# 2023_04_07_SCH_Sensor.net
KiCad netlist of a schematic drawn in EasyEDA
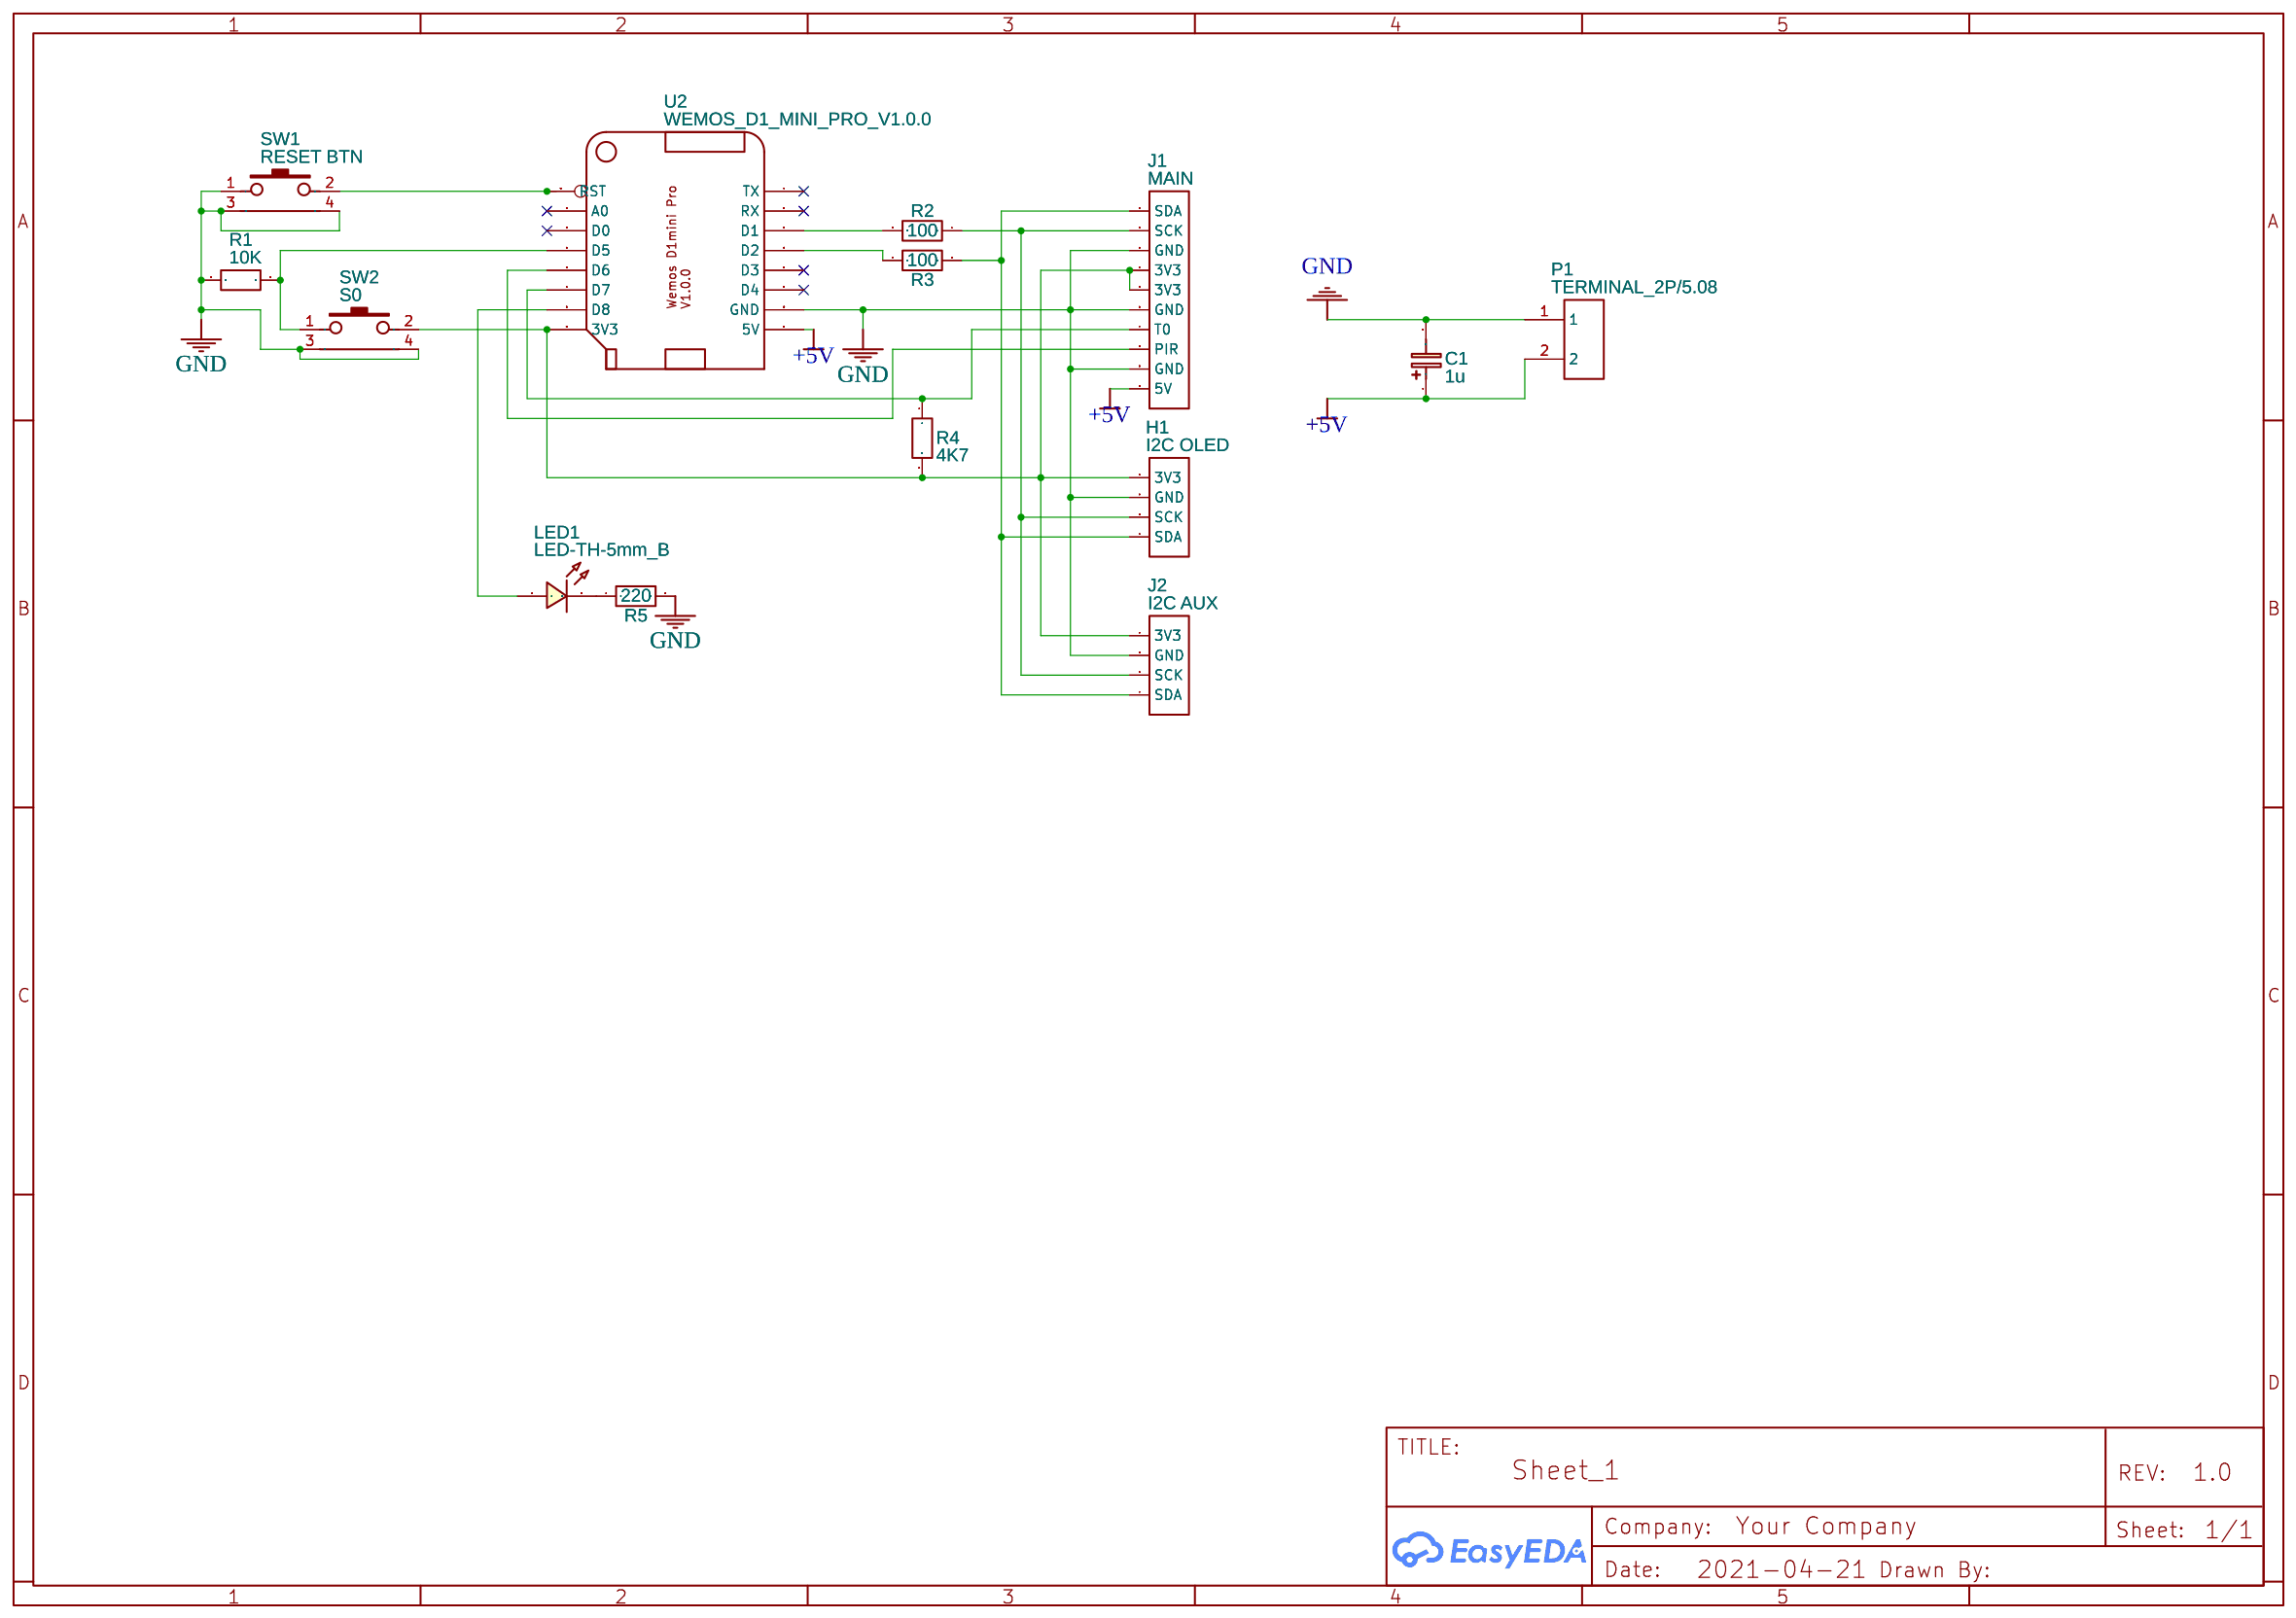
[diagram p0: Main]
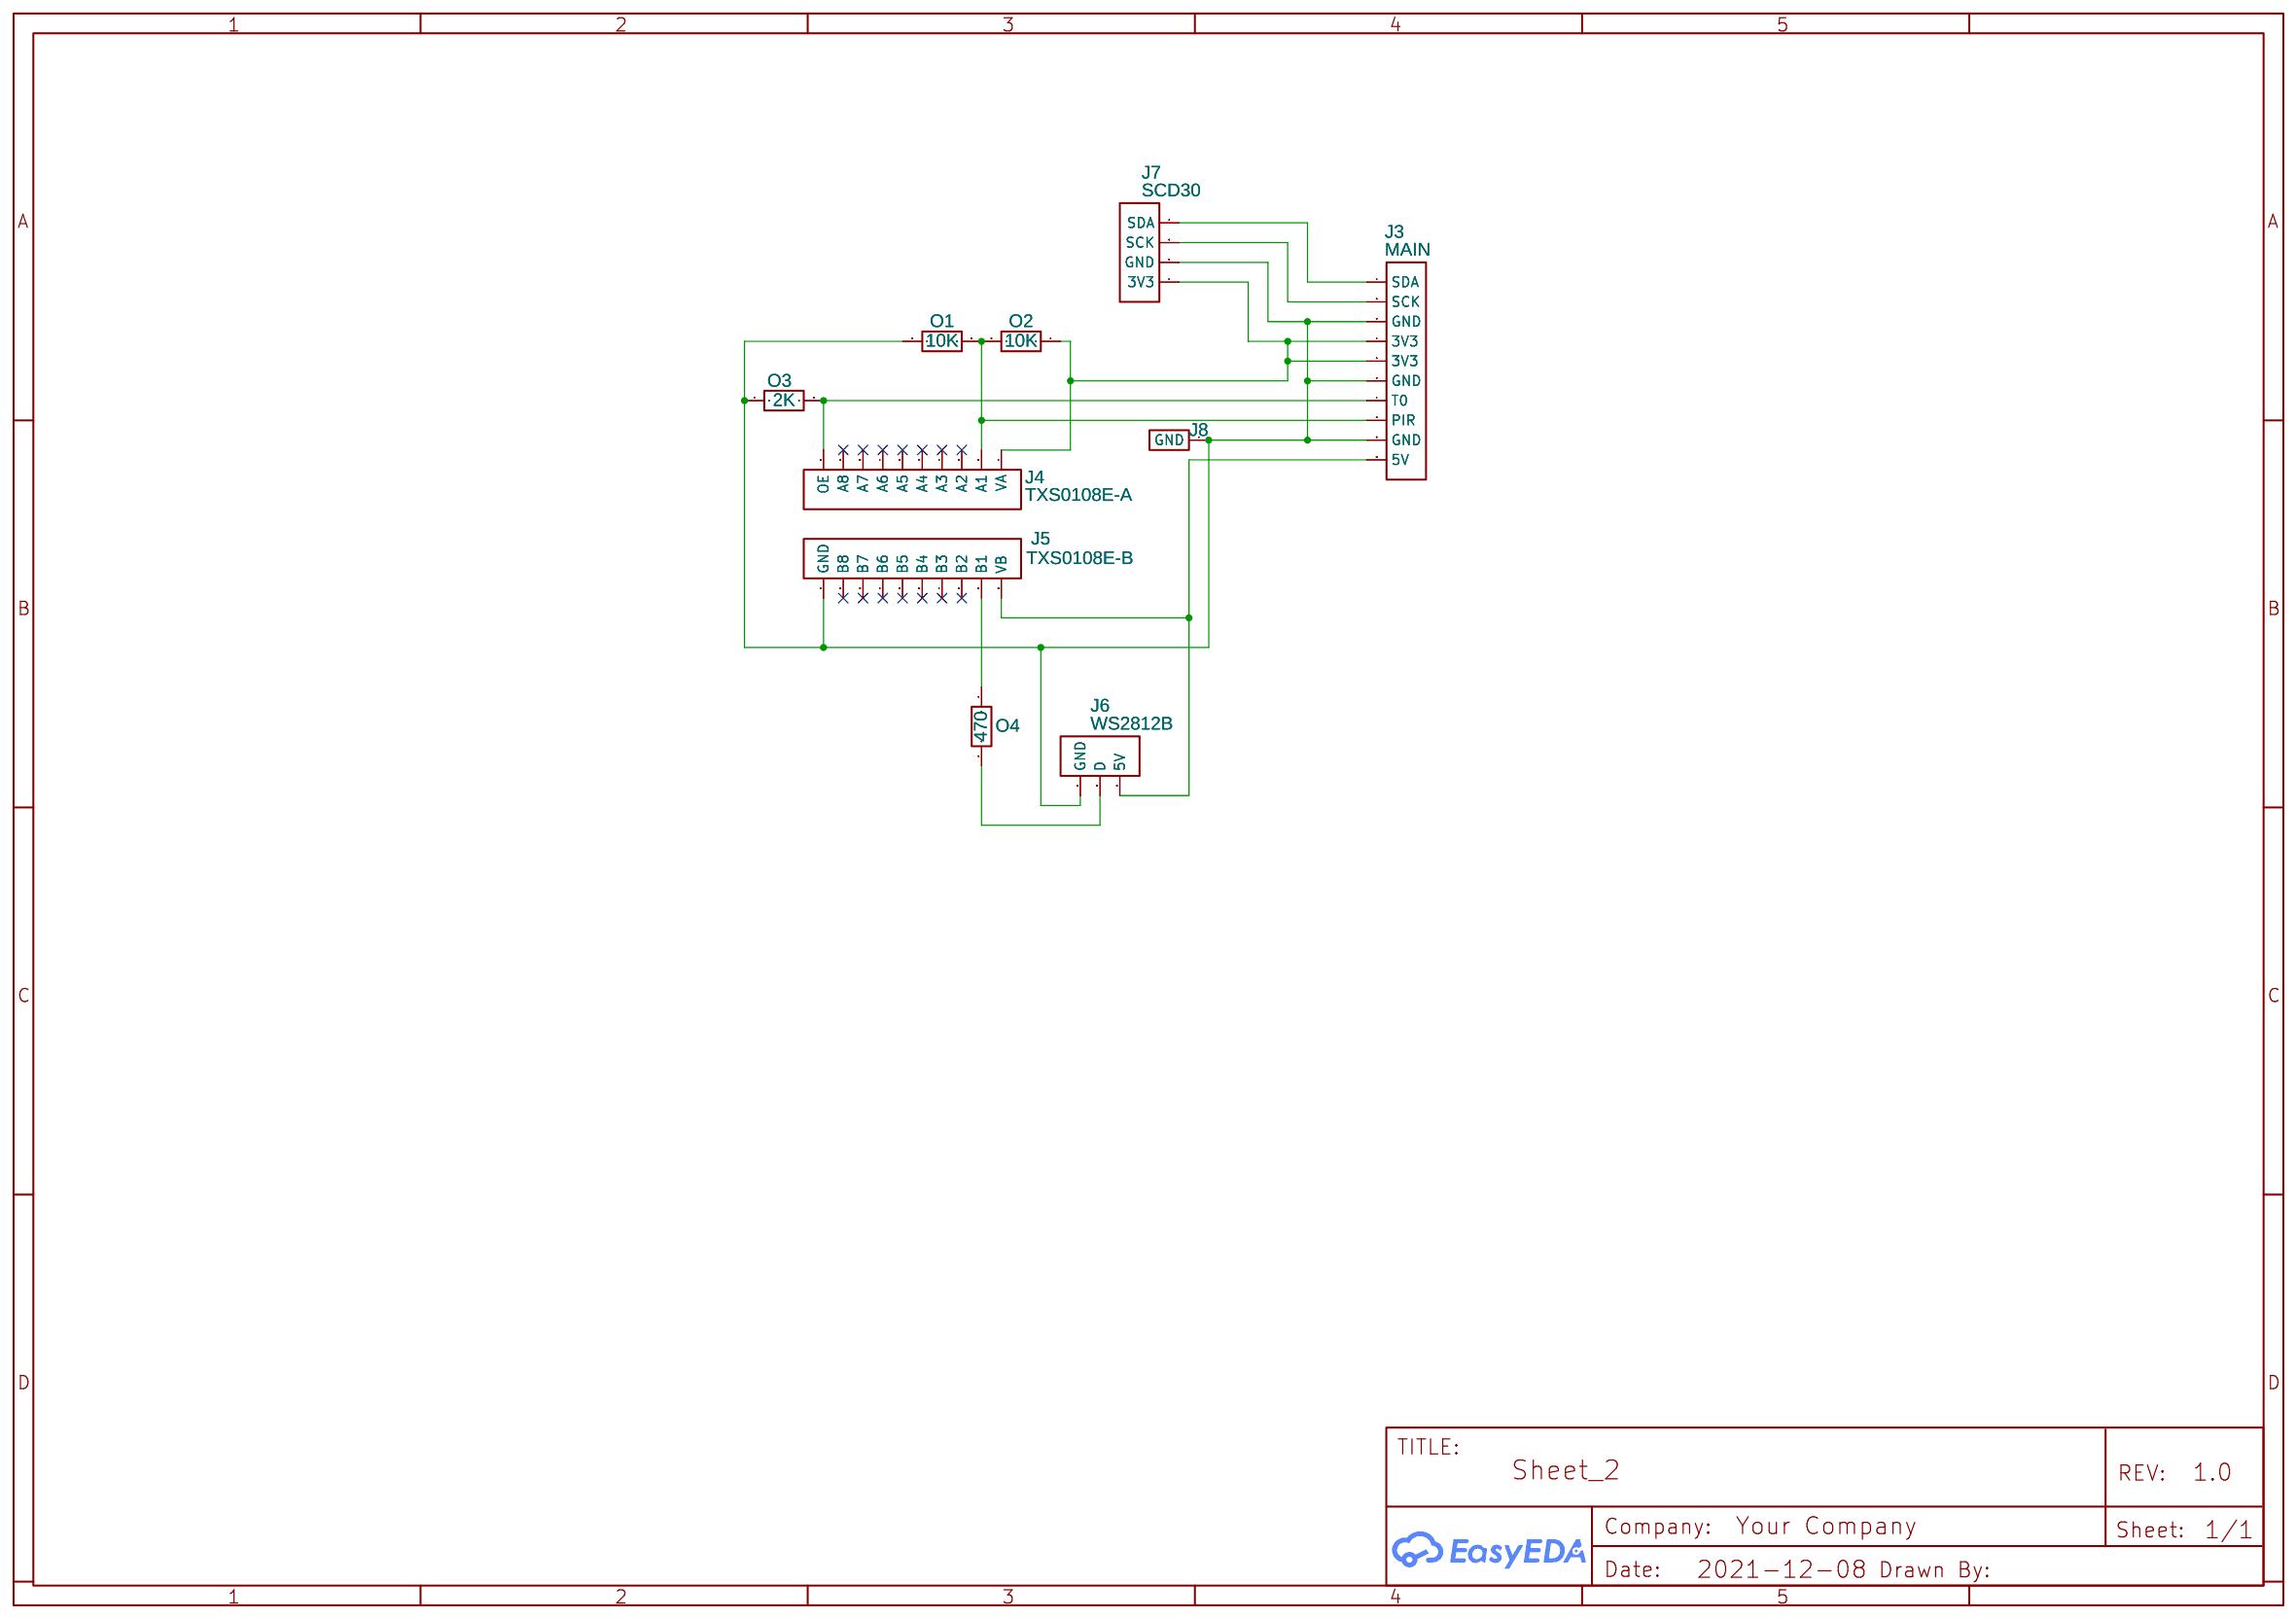
[diagram p1: Aux_C02]

(export (version "E")
  (design (tool "Eeschema 10.0.6"))
  (components
    (comp (ref "C1") (value "1u") (libsource (lib "") (part "CE_TH_D10.0×F5.0_EU")))
    (comp (ref "H1")
      (value "I2C OLED")
      (fields (field (name "BOM_Supplier Part") "C225501"))
      (libsource (lib "") (part "HDR-F-2.54_1x4"))
    )
    (comp (ref "J1")
      (value "MAIN")
      (fields (field (name "BOM_Supplier Part") "C57369"))
      (libsource (lib "") (part "HDR-M-2.54_1x10"))
    )
    (comp (ref "J2")
      (value "I2C AUX")
      (fields (field (name "BOM_Supplier Part") "C124378"))
      (libsource (lib "") (part "HDR-M-2.54_1x4"))
    )
    (comp (ref "LED1") (value "LED-TH-5mm_B") (libsource (lib "") (part "LED-TH-5mm_B")))
    (comp (ref "P1")
      (value "TERMINAL_2P/5.08")
      (fields (field (name "BOM_Manufacturer Part") "Screw terminal 2p"))
      (libsource (lib "") (part "TERMINAL_2P/5.08"))
    )
    (comp (ref "R1") (value "10K") (libsource (lib "") (part "R_AXIAL-0.3_EU_1")))
    (comp (ref "R2") (value "100") (libsource (lib "") (part "R_AXIAL-0.3_EU_1")))
    (comp (ref "R3") (value "100") (libsource (lib "") (part "R_AXIAL-0.3_EU")))
    (comp (ref "R4") (value "4K7") (libsource (lib "") (part "R_AXIAL-0.3_EU_2")))
    (comp (ref "R5") (value "220") (libsource (lib "") (part "R_AXIAL-0.3_EU")))
    (comp (ref "SW1")
      (value "RESET BTN")
      (fields
        (field (name "BOM_Manufacturer Part") "Switch,6*6*9Plastic head,260G, 0.25mm,Side bracket")
        (field (name "BOM_Supplier Part") "C71842")
      )
      (libsource (lib "") (part "Button-6x6x9-Right-Angle"))
    )
    (comp (ref "SW2")
      (value "S0")
      (fields
        (field (name "BOM_Manufacturer Part") "Switch,6*6*9Plastic head,260G, 0.25mm,Side bracket")
        (field (name "BOM_Supplier Part") "C71842")
      )
      (libsource (lib "") (part "Button-6x6x9-Right-Angle"))
    )
    (comp (ref "U2")
      (value "WEMOS_D1_MINI_PRO_V1.0.0")
      (fields
        (field (name "BOM_Manufacturer Part") "WeMos D1 Mini Pro")
        (field (name "BOM_Supplier Part") "undefined")
      )
      (libsource (lib "") (part "WEMOS_D1_MINI_PRO_V1.0.0"))
    )
    (comp (ref "J3")
      (value "MAIN")
      (fields (field (name "BOM_Supplier Part") "C57369"))
      (libsource (lib "") (part "HDR-M-2.54_1x10"))
    )
    (comp (ref "J4")
      (value "TXS0108E-A")
      (fields (field (name "BOM_Supplier Part") "C57369"))
      (libsource (lib "") (part "HDR-M-2.54_1x10_1"))
    )
    (comp (ref "J5")
      (value "TXS0108E-B")
      (fields (field (name "BOM_Supplier Part") "C57369"))
      (libsource (lib "") (part "HDR-M-2.54_1x10_2"))
    )
    (comp (ref "J6")
      (value "WS2812B")
      (fields (field (name "BOM_Supplier Part") "C180248"))
      (libsource (lib "") (part "HDR-M-2.54_1x3"))
    )
    (comp (ref "J7")
      (value "SCD30")
      (fields (field (name "BOM_Supplier Part") "C124378"))
      (libsource (lib "") (part "HDR-M-2.54_1x4"))
    )
    (comp (ref "J8")
      (value "HDR-M-2.54_1x1")
      (fields (field (name "BOM_Supplier Part") "C81276"))
      (libsource (lib "") (part "HDR-M-2.54_1x1"))
    )
    (comp (ref "O1") (value "10K") (libsource (lib "") (part "R_AXIAL-0.3_EU_1")))
    (comp (ref "O2") (value "10K") (libsource (lib "") (part "R_AXIAL-0.3_EU")))
    (comp (ref "O3") (value "2K") (libsource (lib "") (part "R_AXIAL-0.3_EU_1")))
    (comp (ref "O4") (value "470") (libsource (lib "") (part "R_AXIAL-0.3_EU_2")))
  )
  (nets
    (net (code "1") (name "+5V") (class "Default")
      (node (ref "C1") (pin "1") (pinfunction "1_1") (pintype "unspecified"))
      (node (ref "J1") (pin "10") (pinfunction "5V_10") (pintype "unspecified"))
      (node (ref "P1") (pin "2") (pinfunction "2_2") (pintype "unspecified"))
      (node (ref "U2") (pin "5V") (pinfunction "5V_5V") (pintype "unspecified"))
    )
    (net (code "2") (name "GND") (class "Default")
      (node (ref "C1") (pin "2") (pinfunction "2_2") (pintype "unspecified"))
      (node (ref "H1") (pin "2") (pinfunction "GND_2") (pintype "unspecified"))
      (node (ref "J1") (pin "3") (pinfunction "GND_3") (pintype "unspecified"))
      (node (ref "J1") (pin "6") (pinfunction "GND_6") (pintype "unspecified"))
      (node (ref "J1") (pin "9") (pinfunction "GND_9") (pintype "unspecified"))
      (node (ref "J2") (pin "2") (pinfunction "GND_2") (pintype "unspecified"))
      (node (ref "P1") (pin "1") (pinfunction "1_1") (pintype "unspecified"))
      (node (ref "R1") (pin "2") (pinfunction "2_2") (pintype "unspecified"))
      (node (ref "R5") (pin "2") (pinfunction "2_2") (pintype "unspecified"))
      (node (ref "SW1") (pin "1") (pinfunction "1_1") (pintype "input"))
      (node (ref "SW1") (pin "3") (pinfunction "3_3") (pintype "input"))
      (node (ref "SW1") (pin "4") (pinfunction "4_4") (pintype "input"))
      (node (ref "SW2") (pin "3") (pinfunction "3_3") (pintype "input"))
      (node (ref "SW2") (pin "4") (pinfunction "4_4") (pintype "input"))
      (node (ref "U2") (pin "GND") (pinfunction "GND_GND") (pintype "unspecified"))
    )
    (net (code "3") (name "Net-(H1-3V3)") (class "Default")
      (node (ref "H1") (pin "1") (pinfunction "3V3_1") (pintype "unspecified"))
      (node (ref "J1") (pin "4") (pinfunction "3V3_4") (pintype "unspecified"))
      (node (ref "J1") (pin "5") (pinfunction "3V3_5") (pintype "unspecified"))
      (node (ref "J2") (pin "1") (pinfunction "3V3_1") (pintype "unspecified"))
      (node (ref "R4") (pin "2") (pinfunction "2_2") (pintype "unspecified"))
      (node (ref "SW2") (pin "2") (pinfunction "2_2") (pintype "input"))
      (node (ref "U2") (pin "3V3") (pinfunction "3V3_3V3") (pintype "unspecified"))
    )
    (net (code "4") (name "Net-(H1-SCK)") (class "Default")
      (node (ref "H1") (pin "3") (pinfunction "SCK_3") (pintype "unspecified"))
      (node (ref "J1") (pin "2") (pinfunction "SCK_2") (pintype "unspecified"))
      (node (ref "J2") (pin "3") (pinfunction "SCK_3") (pintype "unspecified"))
      (node (ref "R2") (pin "1") (pinfunction "1_1") (pintype "unspecified"))
    )
    (net (code "5") (name "Net-(H1-SDA)") (class "Default")
      (node (ref "H1") (pin "4") (pinfunction "SDA_4") (pintype "unspecified"))
      (node (ref "J1") (pin "1") (pinfunction "SDA_1") (pintype "unspecified"))
      (node (ref "J2") (pin "4") (pinfunction "SDA_4") (pintype "unspecified"))
      (node (ref "R3") (pin "2") (pinfunction "2_2") (pintype "unspecified"))
    )
    (net (code "6") (name "Net-(J1-PIR)") (class "Default")
      (node (ref "J1") (pin "8") (pinfunction "PIR_8") (pintype "unspecified"))
      (node (ref "U2") (pin "D6") (pinfunction "D6_D6") (pintype "unspecified"))
    )
    (net (code "7") (name "Net-(J1-T0)") (class "Default")
      (node (ref "J1") (pin "7") (pinfunction "T0_7") (pintype "unspecified"))
      (node (ref "R4") (pin "1") (pinfunction "1_1") (pintype "unspecified"))
      (node (ref "U2") (pin "D7") (pinfunction "D7_D7") (pintype "unspecified"))
    )
    (net (code "8") (name "Net-(J3-5V)") (class "Default")
      (node (ref "J3") (pin "10") (pinfunction "5V_10") (pintype "unspecified"))
      (node (ref "J5") (pin "10") (pinfunction "VB_10") (pintype "unspecified"))
      (node (ref "J6") (pin "3") (pinfunction "5V_3") (pintype "input"))
    )
    (net (code "9") (name "Net-(J3-PIR)") (class "Default")
      (node (ref "J3") (pin "8") (pinfunction "PIR_8") (pintype "unspecified"))
      (node (ref "J4") (pin "2") (pinfunction "A1_2") (pintype "unspecified"))
      (node (ref "O1") (pin "2") (pinfunction "2_2") (pintype "unspecified"))
      (node (ref "O2") (pin "2") (pinfunction "2_2") (pintype "unspecified"))
    )
    (net (code "10") (name "Net-(J3-SCK)") (class "Default")
      (node (ref "J3") (pin "2") (pinfunction "SCK_2") (pintype "unspecified"))
      (node (ref "J7") (pin "3") (pinfunction "SCK_3") (pintype "unspecified"))
    )
    (net (code "11") (name "Net-(J3-SDA)") (class "Default")
      (node (ref "J3") (pin "1") (pinfunction "SDA_1") (pintype "unspecified"))
      (node (ref "J7") (pin "4") (pinfunction "SDA_4") (pintype "unspecified"))
    )
    (net (code "12") (name "Net-(J3-T0)") (class "Default")
      (node (ref "J3") (pin "7") (pinfunction "T0_7") (pintype "unspecified"))
      (node (ref "J4") (pin "10") (pinfunction "OE_10") (pintype "unspecified"))
      (node (ref "O3") (pin "2") (pinfunction "2_2") (pintype "unspecified"))
    )
    (net (code "13") (name "Net-(J4-VA)") (class "Default")
      (node (ref "J3") (pin "4") (pinfunction "3V3_4") (pintype "unspecified"))
      (node (ref "J3") (pin "5") (pinfunction "3V3_5") (pintype "unspecified"))
      (node (ref "J4") (pin "1") (pinfunction "VA_1") (pintype "unspecified"))
      (node (ref "J7") (pin "1") (pinfunction "3V3_1") (pintype "unspecified"))
      (node (ref "O2") (pin "1") (pinfunction "1_1") (pintype "unspecified"))
    )
    (net (code "14") (name "Net-(J5-B1)") (class "Default")
      (node (ref "J5") (pin "9") (pinfunction "B1_9") (pintype "unspecified"))
      (node (ref "O4") (pin "1") (pinfunction "1_1") (pintype "unspecified"))
    )
    (net (code "15") (name "Net-(J5-GND)") (class "Default")
      (node (ref "J3") (pin "3") (pinfunction "GND_3") (pintype "unspecified"))
      (node (ref "J3") (pin "6") (pinfunction "GND_6") (pintype "unspecified"))
      (node (ref "J3") (pin "9") (pinfunction "GND_9") (pintype "unspecified"))
      (node (ref "J5") (pin "1") (pinfunction "GND_1") (pintype "unspecified"))
      (node (ref "J6") (pin "1") (pinfunction "GND_1") (pintype "input"))
      (node (ref "J7") (pin "2") (pinfunction "GND_2") (pintype "unspecified"))
      (node (ref "J8") (pin "1") (pinfunction "GND_1") (pintype "input"))
      (node (ref "O1") (pin "1") (pinfunction "1_1") (pintype "unspecified"))
      (node (ref "O3") (pin "1") (pinfunction "1_1") (pintype "unspecified"))
    )
    (net (code "16") (name "Net-(J6-D)") (class "Default")
      (node (ref "J6") (pin "2") (pinfunction "D_2") (pintype "input"))
      (node (ref "O4") (pin "2") (pinfunction "2_2") (pintype "unspecified"))
    )
    (net (code "17") (name "Net-(LED1-Pad1)") (class "Default")
      (node (ref "LED1") (pin "1") (pinfunction "1_1") (pintype "unspecified"))
      (node (ref "U2") (pin "D8") (pinfunction "D8_D8") (pintype "unspecified"))
    )
    (net (code "18") (name "Net-(LED1-Pad2)") (class "Default")
      (node (ref "LED1") (pin "2") (pinfunction "2_2") (pintype "unspecified"))
      (node (ref "R5") (pin "1") (pinfunction "1_1") (pintype "unspecified"))
    )
    (net (code "19") (name "Net-(R1-Pad1)") (class "Default")
      (node (ref "R1") (pin "1") (pinfunction "1_1") (pintype "unspecified"))
      (node (ref "SW2") (pin "1") (pinfunction "1_1") (pintype "input"))
      (node (ref "U2") (pin "D5") (pinfunction "D5_D5") (pintype "unspecified"))
    )
    (net (code "20") (name "Net-(R2-Pad2)") (class "Default")
      (node (ref "R2") (pin "2") (pinfunction "2_2") (pintype "unspecified"))
      (node (ref "U2") (pin "D1") (pinfunction "D1_D1") (pintype "unspecified"))
    )
    (net (code "21") (name "Net-(R3-Pad1)") (class "Default")
      (node (ref "R3") (pin "1") (pinfunction "1_1") (pintype "unspecified"))
      (node (ref "U2") (pin "D2") (pinfunction "D2_D2") (pintype "unspecified"))
    )
    (net (code "22") (name "Net-(SW1-Pad2)") (class "Default")
      (node (ref "SW1") (pin "2") (pinfunction "2_2") (pintype "input"))
      (node (ref "U2") (pin "RST") (pinfunction "RST_RST") (pintype "unspecified"))
    )
    (net (code "23") (name "unconnected-(J4-A2-Pad3)") (class "Default")
      (node (ref "J4") (pin "3") (pinfunction "A2_3") (pintype "unspecified+no_connect"))
    )
    (net (code "24") (name "unconnected-(J4-A3-Pad4)") (class "Default")
      (node (ref "J4") (pin "4") (pinfunction "A3_4") (pintype "unspecified+no_connect"))
    )
    (net (code "25") (name "unconnected-(J4-A4-Pad5)") (class "Default")
      (node (ref "J4") (pin "5") (pinfunction "A4_5") (pintype "unspecified+no_connect"))
    )
    (net (code "26") (name "unconnected-(J4-A5-Pad6)") (class "Default")
      (node (ref "J4") (pin "6") (pinfunction "A5_6") (pintype "unspecified+no_connect"))
    )
    (net (code "27") (name "unconnected-(J4-A6-Pad7)") (class "Default")
      (node (ref "J4") (pin "7") (pinfunction "A6_7") (pintype "unspecified+no_connect"))
    )
    (net (code "28") (name "unconnected-(J4-A7-Pad8)") (class "Default")
      (node (ref "J4") (pin "8") (pinfunction "A7_8") (pintype "unspecified+no_connect"))
    )
    (net (code "29") (name "unconnected-(J4-A8-Pad9)") (class "Default")
      (node (ref "J4") (pin "9") (pinfunction "A8_9") (pintype "unspecified+no_connect"))
    )
    (net (code "30") (name "unconnected-(J5-B2-Pad8)") (class "Default")
      (node (ref "J5") (pin "8") (pinfunction "B2_8") (pintype "unspecified+no_connect"))
    )
    (net (code "31") (name "unconnected-(J5-B3-Pad7)") (class "Default")
      (node (ref "J5") (pin "7") (pinfunction "B3_7") (pintype "unspecified+no_connect"))
    )
    (net (code "32") (name "unconnected-(J5-B4-Pad6)") (class "Default")
      (node (ref "J5") (pin "6") (pinfunction "B4_6") (pintype "unspecified+no_connect"))
    )
    (net (code "33") (name "unconnected-(J5-B5-Pad5)") (class "Default")
      (node (ref "J5") (pin "5") (pinfunction "B5_5") (pintype "unspecified+no_connect"))
    )
    (net (code "34") (name "unconnected-(J5-B6-Pad4)") (class "Default")
      (node (ref "J5") (pin "4") (pinfunction "B6_4") (pintype "unspecified+no_connect"))
    )
    (net (code "35") (name "unconnected-(J5-B7-Pad3)") (class "Default")
      (node (ref "J5") (pin "3") (pinfunction "B7_3") (pintype "unspecified+no_connect"))
    )
    (net (code "36") (name "unconnected-(J5-B8-Pad2)") (class "Default")
      (node (ref "J5") (pin "2") (pinfunction "B8_2") (pintype "unspecified+no_connect"))
    )
    (net (code "37") (name "unconnected-(U2-PadA0)") (class "Default")
      (node (ref "U2") (pin "A0") (pinfunction "A0_A0") (pintype "unspecified+no_connect"))
    )
    (net (code "38") (name "unconnected-(U2-PadD0)") (class "Default")
      (node (ref "U2") (pin "D0") (pinfunction "D0_D0") (pintype "unspecified+no_connect"))
    )
    (net (code "39") (name "unconnected-(U2-PadD3)") (class "Default")
      (node (ref "U2") (pin "D3") (pinfunction "D3_D3") (pintype "unspecified+no_connect"))
    )
    (net (code "40") (name "unconnected-(U2-PadD4)") (class "Default")
      (node (ref "U2") (pin "D4") (pinfunction "D4_D4") (pintype "unspecified+no_connect"))
    )
    (net (code "41") (name "unconnected-(U2-PadRX)") (class "Default")
      (node (ref "U2") (pin "RX") (pinfunction "RX_RX") (pintype "unspecified+no_connect"))
    )
    (net (code "42") (name "unconnected-(U2-PadTX)") (class "Default")
      (node (ref "U2") (pin "TX") (pinfunction "TX_TX") (pintype "unspecified+no_connect"))
    )
  )
)
